# Microcontroller.net
KiCad netlist of a schematic drawn in Altium Designer
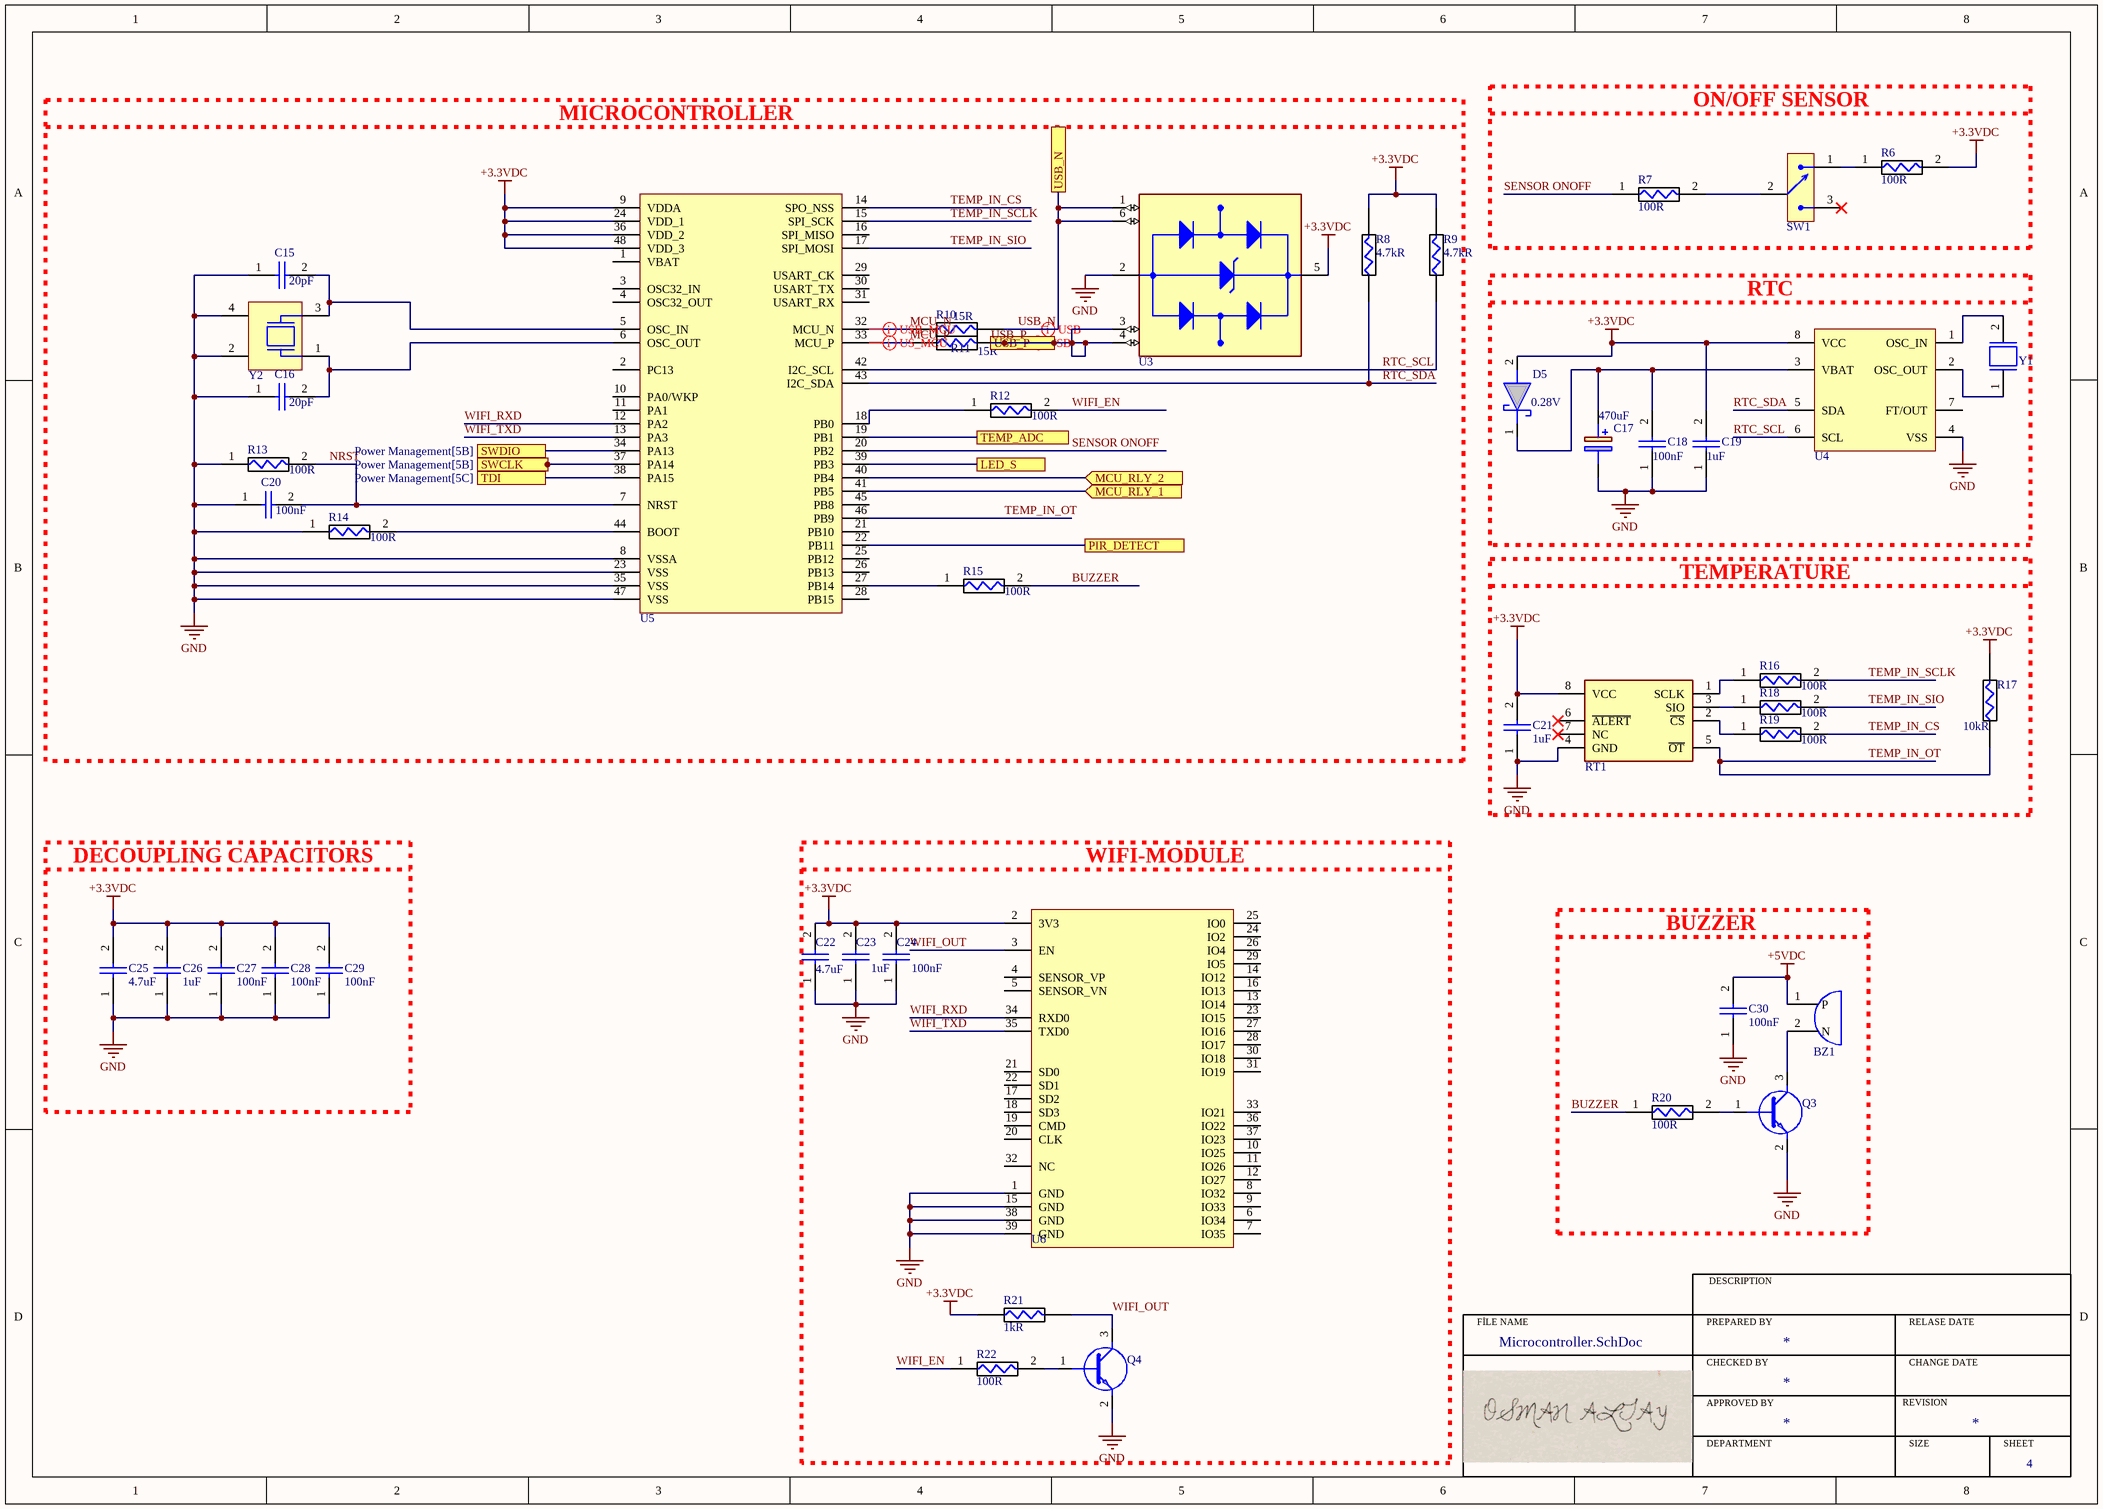
[diagram p0: Microcontroller.SchDoc]

(export (version "E")
  (design (tool "Eeschema 10.0.6"))
  (components
    (comp (ref "BZ1")
      (value "CMI-9605IC-0580T")
      (footprint "CMI-9605IC-0580T")
      (description "Audio Buzzer Magnetic 3VDC 7VDC 30mA 5VDC 85dB 2600Hz to 2800Hz Through Hole Pin Box")
      (fields (field (name "MANUFACTURER") "CUI Devices"))
      (libsource (lib "udemy_library") (part "CMI-9605IC-0580T"))
    )
    (comp (ref "C15")
      (value "20pF")
      (footprint "CAP_0603")
      (description "CAP CER 20pF %5 0603")
      (fields
        (field (name "MANUFACTURER") "Samsung")
        (field (name "MANUFACTURER PART NUMBER") "CL10C200JB8NNNC")
        (field (name "DESIGNED BY") "Osman")
      )
      (libsource (lib "udemy_library") (part "CAP CER 20pF 0603"))
    )
    (comp (ref "C16")
      (value "20pF")
      (footprint "CAP_0603")
      (description "CAP CER 20pF %5 0603")
      (fields
        (field (name "MANUFACTURER") "Samsung")
        (field (name "MANUFACTURER PART NUMBER") "CL10C200JB8NNNC")
        (field (name "DESIGNED BY") "Osman")
      )
      (libsource (lib "udemy_library") (part "CAP CER 20pF 0603"))
    )
    (comp (ref "C17")
      (value "470uF")
      (footprint "ESH477M050AH4AA")
      (description "Cap, 470UF, 50V, Alu Elec, Radial")
      (fields
        (field (name "MANUFACTURER") "KEMET")
        (field (name "MANUFACTURER PART NUMBER") "ESH477M050AH4AA")
        (field (name "DESIGNED BY") "Osman")
      )
      (libsource (lib "udemy_library") (part "CAP ALU 470uF"))
    )
    (comp (ref "C18")
      (value "100nF")
      (footprint "CAP_0805")
      (description "CL21B104KBCNNNC")
      (fields
        (field (name "MANUFACTURER") "Samsung")
        (field (name "TOLERANCE") "10%")
        (field (name "DESIGNED BY") "OSMAN")
      )
      (libsource (lib "udemy_library") (part "CAP CER 100nF 0805"))
    )
    (comp (ref "C19")
      (value "1uF")
      (footprint "CAP_0805")
      (description "CAP CER 1uF %10 0805")
      (fields
        (field (name "MANUFACTURER") "Samsung")
        (field (name "MANUFACTURER PART NUMBER") "CL21B105KBFNNNE")
        (field (name "DESIGNED BY") "Osman")
      )
      (libsource (lib "udemy_library") (part "CAP CER 1uF 0805"))
    )
    (comp (ref "C20")
      (value "100nF")
      (footprint "CAP_0603")
      (description "Capacitor, 0.1UF, 100V, MLCC, 0603;")
      (fields
        (field (name "MANUFACTURER") "KEMET")
        (field (name "MANUFACTURER PART NUMBER") "C0603C104K1RACTU")
        (field (name "DESIGNED BY") "Osman")
      )
      (libsource (lib "udemy_library") (part "CAP CER 100nf 0603"))
    )
    (comp (ref "C21")
      (value "1uF")
      (footprint "CAP_0805")
      (description "CAP CER 1uF %10 0805")
      (fields
        (field (name "MANUFACTURER") "Samsung")
        (field (name "MANUFACTURER PART NUMBER") "CL21B105KBFNNNE")
        (field (name "DESIGNED BY") "Osman")
      )
      (libsource (lib "udemy_library") (part "CAP CER 1uF 0805"))
    )
    (comp (ref "C22")
      (value "4.7uF")
      (footprint "CAP_0805")
      (description "CAP CER 4.7uF %10 0805")
      (fields
        (field (name "MANUFACTURER") "Samsung")
        (field (name "MANUFACTURER PART NUMBER") "CL21A475KAQNNNE")
      )
      (libsource (lib "udemy_library") (part "CAP CER 4.7uF 0805"))
    )
    (comp (ref "C23")
      (value "1uF")
      (footprint "CAP_0805")
      (description "CAP CER 1uF %10 0805")
      (fields
        (field (name "MANUFACTURER") "Samsung")
        (field (name "MANUFACTURER PART NUMBER") "CL21B105KBFNNNE")
        (field (name "DESIGNED BY") "Osman")
      )
      (libsource (lib "udemy_library") (part "CAP CER 1uF 0805"))
    )
    (comp (ref "C24")
      (value "100nF")
      (footprint "CAP_0603")
      (description "Capacitor, 0.1UF, 100V, MLCC, 0603;")
      (fields
        (field (name "MANUFACTURER") "KEMET")
        (field (name "MANUFACTURER PART NUMBER") "C0603C104K1RACTU")
        (field (name "DESIGNED BY") "Osman")
      )
      (libsource (lib "udemy_library") (part "CAP CER 100nf 0603"))
    )
    (comp (ref "C25")
      (value "4.7uF")
      (footprint "CAP_0805")
      (description "CAP CER 4.7uF %10 0805")
      (fields
        (field (name "MANUFACTURER") "Samsung")
        (field (name "MANUFACTURER PART NUMBER") "CL21A475KAQNNNE")
      )
      (libsource (lib "udemy_library") (part "CAP CER 4.7uF 0805"))
    )
    (comp (ref "C26")
      (value "1uF")
      (footprint "CAP_0805")
      (description "CAP CER 1uF %10 0805")
      (fields
        (field (name "MANUFACTURER") "Samsung")
        (field (name "MANUFACTURER PART NUMBER") "CL21B105KBFNNNE")
        (field (name "DESIGNED BY") "Osman")
      )
      (libsource (lib "udemy_library") (part "CAP CER 1uF 0805"))
    )
    (comp (ref "C27")
      (value "100nF")
      (footprint "CAP_0603")
      (description "Capacitor, 0.1UF, 100V, MLCC, 0603;")
      (fields
        (field (name "MANUFACTURER") "KEMET")
        (field (name "MANUFACTURER PART NUMBER") "C0603C104K1RACTU")
        (field (name "DESIGNED BY") "Osman")
      )
      (libsource (lib "udemy_library") (part "CAP CER 100nf 0603"))
    )
    (comp (ref "C28")
      (value "100nF")
      (footprint "CAP_0603")
      (description "Capacitor, 0.1UF, 100V, MLCC, 0603;")
      (fields
        (field (name "MANUFACTURER") "KEMET")
        (field (name "MANUFACTURER PART NUMBER") "C0603C104K1RACTU")
        (field (name "DESIGNED BY") "Osman")
      )
      (libsource (lib "udemy_library") (part "CAP CER 100nf 0603"))
    )
    (comp (ref "C29")
      (value "100nF")
      (footprint "CAP_0603")
      (description "Capacitor, 0.1UF, 100V, MLCC, 0603;")
      (fields
        (field (name "MANUFACTURER") "KEMET")
        (field (name "MANUFACTURER PART NUMBER") "C0603C104K1RACTU")
        (field (name "DESIGNED BY") "Osman")
      )
      (libsource (lib "udemy_library") (part "CAP CER 100nf 0603"))
    )
    (comp (ref "C30")
      (value "100nF")
      (footprint "CAP_0805")
      (description "CL21B104KBCNNNC")
      (fields
        (field (name "MANUFACTURER") "Samsung")
        (field (name "TOLERANCE") "10%")
        (field (name "DESIGNED BY") "OSMAN")
      )
      (libsource (lib "udemy_library") (part "CAP CER 100nF 0805"))
    )
    (comp (ref "D5")
      (value "RB521CS30L,315")
      (footprint "SOD882")
      (description "100MA Low Vf Mega Schottky Barri")
      (fields
        (field (name "MANUFACTURER") "Nexperia")
        (field (name "MANUFACTURER PART NUMBER") "RB521CS30L315")
        (field (name "FORWARD VOLTAGE") "0.28V")
      )
      (libsource (lib "udemy_library") (part "RB521CS30L,315"))
    )
    (comp (ref "Q3")
      (value "MMBT3904-7-F")
      (footprint "SOT23-3")
      (description "Transistor General Purpose BJT NPN 40 Volt 0.2A Automotive 3-Pin SOT-23")
      (fields (field (name "MANUFACTURER") "Diodes Zetex") (field (name "DESIGNED BY") "Osman"))
      (libsource (lib "udemy_library") (part "MMBT3904-7-F"))
    )
    (comp (ref "Q4")
      (value "MMBT3904-7-F")
      (footprint "SOT23-3")
      (description "Transistor General Purpose BJT NPN 40 Volt 0.2A Automotive 3-Pin SOT-23")
      (fields (field (name "MANUFACTURER") "Diodes Zetex") (field (name "DESIGNED BY") "Osman"))
      (libsource (lib "udemy_library") (part "MMBT3904-7-F"))
    )
    (comp (ref "R6")
      (value "100R")
      (footprint "RES_0603")
      (description "SMD Chip Resistor, 100 Ohm, ± 1%, 100 mW, 0603 [1608 Metric], Thick Film, General Purpose")
      (fields
        (field (name "MANUFACTURER") "Yageo")
        (field (name "MANUFACTURER PART NUMBER") "RC0603FR-07100RL")
      )
      (libsource (lib "udemy_library") (part "RES 100 OHM 0603"))
    )
    (comp (ref "R7")
      (value "100R")
      (footprint "RES_0603")
      (description "SMD Chip Resistor, 100 Ohm, ± 1%, 100 mW, 0603 [1608 Metric], Thick Film, General Purpose")
      (fields
        (field (name "MANUFACTURER") "Yageo")
        (field (name "MANUFACTURER PART NUMBER") "RC0603FR-07100RL")
      )
      (libsource (lib "udemy_library") (part "RES 100 OHM 0603"))
    )
    (comp (ref "R8")
      (value "4.7kR")
      (footprint "RES_0603")
      (description "SMD Chip Resistor, 4.7 kOhm, ± 5%, 100 mW, 0603 [1608 Metric], Thick Film, General Purpose")
      (fields
        (field (name "MANUFACTURER") "Yageo")
        (field (name "MANUFACTURER PART NUMBER") "RC0603JR-074K7L")
      )
      (libsource (lib "udemy_library") (part "RES 4K7 OHM 0603"))
    )
    (comp (ref "R9")
      (value "4.7kR")
      (footprint "RES_0603")
      (description "SMD Chip Resistor, 4.7 kOhm, ± 5%, 100 mW, 0603 [1608 Metric], Thick Film, General Purpose")
      (fields
        (field (name "MANUFACTURER") "Yageo")
        (field (name "MANUFACTURER PART NUMBER") "RC0603JR-074K7L")
      )
      (libsource (lib "udemy_library") (part "RES 4K7 OHM 0603"))
    )
    (comp (ref "R10")
      (value "15R")
      (footprint "RES_0603")
      (description "SMD Chip Resistor, 15 Ohm, ± 5%, 100 mW, 0603 [1608 Metric], Thick Film, General Purpose")
      (fields
        (field (name "MANUFACTURER") "Yageo")
        (field (name "MANUFACTURER PART NUMBER") "RC0603JR-0715RL")
      )
      (libsource (lib "udemy_library") (part "RES 15 OHM 0603"))
    )
    (comp (ref "R11")
      (value "15R")
      (footprint "RES_0603")
      (description "SMD Chip Resistor, 15 Ohm, ± 5%, 100 mW, 0603 [1608 Metric], Thick Film, General Purpose")
      (fields
        (field (name "MANUFACTURER") "Yageo")
        (field (name "MANUFACTURER PART NUMBER") "RC0603JR-0715RL")
      )
      (libsource (lib "udemy_library") (part "RES 15 OHM 0603"))
    )
    (comp (ref "R12")
      (value "100R")
      (footprint "RES_0603")
      (description "SMD Chip Resistor, 100 Ohm, ± 1%, 100 mW, 0603 [1608 Metric], Thick Film, General Purpose")
      (fields
        (field (name "MANUFACTURER") "Yageo")
        (field (name "MANUFACTURER PART NUMBER") "RC0603FR-07100RL")
      )
      (libsource (lib "udemy_library") (part "RES 100 OHM 0603"))
    )
    (comp (ref "R13")
      (value "100R")
      (footprint "RES_0603")
      (description "SMD Chip Resistor, 100 Ohm, ± 1%, 100 mW, 0603 [1608 Metric], Thick Film, General Purpose")
      (fields
        (field (name "MANUFACTURER") "Yageo")
        (field (name "MANUFACTURER PART NUMBER") "RC0603FR-07100RL")
      )
      (libsource (lib "udemy_library") (part "RES 100 OHM 0603"))
    )
    (comp (ref "R14")
      (value "100R")
      (footprint "RES_0603")
      (description "SMD Chip Resistor, 100 Ohm, ± 1%, 100 mW, 0603 [1608 Metric], Thick Film, General Purpose")
      (fields
        (field (name "MANUFACTURER") "Yageo")
        (field (name "MANUFACTURER PART NUMBER") "RC0603FR-07100RL")
      )
      (libsource (lib "udemy_library") (part "RES 100 OHM 0603"))
    )
    (comp (ref "R15")
      (value "100R")
      (footprint "RES_0603")
      (description "SMD Chip Resistor, 100 Ohm, ± 1%, 100 mW, 0603 [1608 Metric], Thick Film, General Purpose")
      (fields
        (field (name "MANUFACTURER") "Yageo")
        (field (name "MANUFACTURER PART NUMBER") "RC0603FR-07100RL")
      )
      (libsource (lib "udemy_library") (part "RES 100 OHM 0603"))
    )
    (comp (ref "R16")
      (value "100R")
      (footprint "RES_0603")
      (description "SMD Chip Resistor, 100 Ohm, ± 1%, 100 mW, 0603 [1608 Metric], Thick Film, General Purpose")
      (fields
        (field (name "MANUFACTURER") "Yageo")
        (field (name "MANUFACTURER PART NUMBER") "RC0603FR-07100RL")
      )
      (libsource (lib "udemy_library") (part "RES 100 OHM 0603"))
    )
    (comp (ref "R17")
      (value "10kR")
      (footprint "RES_0603")
      (description "RES 10K OHM %10 0603")
      (fields
        (field (name "MANUFACTURER") "Yageo")
        (field (name "MANUFACTURER PART NUMBER") "RC0603FR-0710KL")
        (field (name "DESIGNED NY") "Osman")
      )
      (libsource (lib "udemy_library") (part "RES 10K Ohm 0603"))
    )
    (comp (ref "R18")
      (value "100R")
      (footprint "RES_0603")
      (description "SMD Chip Resistor, 100 Ohm, ± 1%, 100 mW, 0603 [1608 Metric], Thick Film, General Purpose")
      (fields
        (field (name "MANUFACTURER") "Yageo")
        (field (name "MANUFACTURER PART NUMBER") "RC0603FR-07100RL")
      )
      (libsource (lib "udemy_library") (part "RES 100 OHM 0603"))
    )
    (comp (ref "R19")
      (value "100R")
      (footprint "RES_0603")
      (description "SMD Chip Resistor, 100 Ohm, ± 1%, 100 mW, 0603 [1608 Metric], Thick Film, General Purpose")
      (fields
        (field (name "MANUFACTURER") "Yageo")
        (field (name "MANUFACTURER PART NUMBER") "RC0603FR-07100RL")
      )
      (libsource (lib "udemy_library") (part "RES 100 OHM 0603"))
    )
    (comp (ref "R20")
      (value "100R")
      (footprint "RES_0603")
      (description "SMD Chip Resistor, 100 Ohm, ± 1%, 100 mW, 0603 [1608 Metric], Thick Film, General Purpose")
      (fields
        (field (name "MANUFACTURER") "Yageo")
        (field (name "MANUFACTURER PART NUMBER") "RC0603FR-07100RL")
      )
      (libsource (lib "udemy_library") (part "RES 100 OHM 0603"))
    )
    (comp (ref "R21")
      (value "1kR")
      (footprint "RES_0603")
      (description "Res Thick Film 0201 1K Ohm 5% 0.05W(1/20W) ±200ppm/C Pad SMD T/R")
      (fields
        (field (name "MANUFACTURER") "Yageo")
        (field (name "MANUFACTURER PART NUMBER") "RC0201JR-071KL")
      )
      (libsource (lib "udemy_library") (part "RES 1K OHM 0603"))
    )
    (comp (ref "R22")
      (value "100R")
      (footprint "RES_0603")
      (description "SMD Chip Resistor, 100 Ohm, ± 1%, 100 mW, 0603 [1608 Metric], Thick Film, General Purpose")
      (fields
        (field (name "MANUFACTURER") "Yageo")
        (field (name "MANUFACTURER PART NUMBER") "RC0603FR-07100RL")
      )
      (libsource (lib "udemy_library") (part "RES 100 OHM 0603"))
    )
    (comp (ref "RT1")
      (value "MAX6662MSA+")
      (footprint "MAX6662MSA+")
      (description "Temp Sensor Digital Serial (3-Wire, SPI) 8-Pin SOIC N Tube")
      (fields (field (name "MANUFACTURER") "Maxim") (field (name "DESIGNED BY") "Osman"))
      (libsource (lib "udemy_library") (part "MAX6662MSA+"))
    )
    (comp (ref "SW1")
      (value "EG1215AA")
      (footprint "SW_EG1215AA")
      (description "Slide Switch, SPDT, 0.025A, 24V, SMD")
      (fields (field (name "MANUFACTURER") "E-Switch"))
      (libsource (lib "udemy_library") (part "EG1215AA"))
    )
    (comp (ref "U3")
      (value "USBLC6-2SC6")
      (footprint "SOT23-6")
      (description "USBLC6 Series 2 Line 6 V Uni / Bi-Directional ESD Protection - SOT-23-6")
      (fields (field (name "MANUFACTURER") "STMicroelectronics"))
      (libsource (lib "udemy_library") (part "USBLC6-2SC6"))
    )
    (comp (ref "U4")
      (value "M41T00M6F")
      (footprint "M41T00")
      (description "Real-time Clocks Clock/Calendar I2C, 2-Wire Serial 70uA @ 2V ~ 5.5V SOIC-8_150mil RoHS")
      (fields (field (name "MANUFACTURER") "STMicroelectronics"))
      (libsource (lib "udemy_library") (part "M41T00"))
    )
    (comp (ref "U5")
      (value "STM32F103C6T6A")
      (footprint "LQFP-48")
      (description "MCU 32-bit STM32F ARM Cortex M3 RISC 32KB Flash 2.5V/3.3V 48-Pin LQFP Tray")
      (fields (field (name "MANUFACTURER") "STMicroelectronics"))
      (libsource (lib "udemy_library") (part "STM32F103C6T6A"))
    )
    (comp (ref "U6")
      (value "ESP32-WROOM-32")
      (footprint "ESP32")
      (description "SMD module, ESP32-D0WD-V3, ESP32 ECO V3, 4 MB SPI flash, PCB antenna")
      (fields
        (field (name "MANUFACTURER") "Espressif Systems")
        (field (name "MANUFACTURER PART NUMBER") "ESP32-WROOM-32E(M113EH3200PH3Q0)")
        (field (name "DESIGNED NY") "Osman")
      )
      (libsource (lib "udemy_library") (part "ESP32-WROOM-32"))
    )
    (comp (ref "Y1")
      (value "ABS05-32.768KHZ-T")
      (footprint "ABS05")
      (description "CRYSTAL 32.768kHz ±20ppm Crystal 12.5pF 90 kOhm -40°C ^ 85°C Surface Mount 2-SMD")
      (fields (field (name "MANUFACTURER") "Abracon") (field (name "TOLERANCE") "20ppm"))
      (libsource (lib "udemy_library") (part "Crystal 32768KHz"))
    )
    (comp (ref "Y2")
      (value "ECS-160-20-30B-TR")
      (footprint "ECS")
      (description "Crystal 16MHz ±30ppm (Tol) ±50ppm (Stability) 20pF FUND 50Ohm 4-Pin Mini-SMD T/R")
      (fields (field (name "MANUFACTURER") "ECS International"))
      (libsource (lib "udemy_library") (part "Crystal 16MHz"))
    )
  )
  (nets
    (net (code "1") (name "+3.3VDC") (class "Default")
      (node (ref "C19") (pin "2") (pinfunction "2_2") (pintype "passive"))
      (node (ref "C21") (pin "2") (pinfunction "2_2") (pintype "passive"))
      (node (ref "C22") (pin "2") (pinfunction "2_2") (pintype "passive"))
      (node (ref "C23") (pin "2") (pinfunction "2_2") (pintype "passive"))
      (node (ref "C24") (pin "2") (pinfunction "2_2") (pintype "passive"))
      (node (ref "C25") (pin "2") (pinfunction "2_2") (pintype "passive"))
      (node (ref "C26") (pin "2") (pinfunction "2_2") (pintype "passive"))
      (node (ref "C27") (pin "2") (pinfunction "2_2") (pintype "passive"))
      (node (ref "C28") (pin "2") (pinfunction "2_2") (pintype "passive"))
      (node (ref "C29") (pin "2") (pinfunction "2_2") (pintype "passive"))
      (node (ref "D5") (pin "2") (pinfunction "A_2") (pintype "passive"))
      (node (ref "R17") (pin "2") (pinfunction "2_2") (pintype "passive"))
      (node (ref "R21") (pin "1") (pinfunction "1_1") (pintype "passive"))
      (node (ref "R6") (pin "2") (pinfunction "2_2") (pintype "passive"))
      (node (ref "R8") (pin "2") (pinfunction "2_2") (pintype "passive"))
      (node (ref "R9") (pin "2") (pinfunction "2_2") (pintype "passive"))
      (node (ref "RT1") (pin "8") (pinfunction "VCC_8") (pintype "passive"))
      (node (ref "U3") (pin "5") (pinfunction "VBUS_5") (pintype "power_in"))
      (node (ref "U4") (pin "8") (pinfunction "VCC_8") (pintype "passive"))
      (node (ref "U5") (pin "24") (pinfunction "VDD_1_24") (pintype "passive"))
      (node (ref "U5") (pin "36") (pinfunction "VDD_2_36") (pintype "passive"))
      (node (ref "U5") (pin "48") (pinfunction "VDD_3_48") (pintype "passive"))
      (node (ref "U5") (pin "9") (pinfunction "VDDA_9") (pintype "passive"))
      (node (ref "U6") (pin "2") (pinfunction "3V3_2") (pintype "passive"))
    )
    (net (code "2") (name "+5VDC") (class "Default")
      (node (ref "BZ1") (pin "1") (pinfunction "P_1") (pintype "passive"))
      (node (ref "C30") (pin "2") (pinfunction "2_2") (pintype "passive"))
    )
    (net (code "3") (name "/BUZZER") (class "Default")
      (node (ref "R15") (pin "2") (pinfunction "2_2") (pintype "passive"))
      (node (ref "R20") (pin "1") (pinfunction "1_1") (pintype "passive"))
    )
    (net (code "4") (name "/LED_S") (class "Default")
      (node (ref "U5") (pin "39") (pinfunction "PB3_39") (pintype "passive"))
    )
    (net (code "5") (name "/MCU_N") (class "Default")
      (node (ref "R10") (pin "1") (pinfunction "1_1") (pintype "passive"))
      (node (ref "U5") (pin "32") (pinfunction "MCU_N_32") (pintype "passive"))
    )
    (net (code "6") (name "/MCU_P") (class "Default")
      (node (ref "R11") (pin "1") (pinfunction "1_1") (pintype "passive"))
      (node (ref "U5") (pin "33") (pinfunction "MCU_P_33") (pintype "passive"))
    )
    (net (code "7") (name "/MCU_RLY_1") (class "Default")
      (node (ref "U5") (pin "41") (pinfunction "PB5_41") (pintype "passive"))
    )
    (net (code "8") (name "/MCU_RLY_2") (class "Default")
      (node (ref "U5") (pin "40") (pinfunction "PB4_40") (pintype "passive"))
    )
    (net (code "9") (name "/NRST") (class "Default")
      (node (ref "C20") (pin "2") (pinfunction "2_2") (pintype "passive"))
      (node (ref "R13") (pin "2") (pinfunction "2_2") (pintype "passive"))
      (node (ref "U5") (pin "7") (pinfunction "NRST_7") (pintype "passive"))
    )
    (net (code "10") (name "/PIR_DETECT") (class "Default")
      (node (ref "U5") (pin "22") (pinfunction "PB11_22") (pintype "passive"))
    )
    (net (code "11") (name "/RTC_SCL") (class "Default")
      (node (ref "R9") (pin "1") (pinfunction "1_1") (pintype "passive"))
      (node (ref "U4") (pin "6") (pinfunction "SCL_6") (pintype "passive"))
      (node (ref "U5") (pin "42") (pinfunction "I2C_SCL_42") (pintype "passive"))
    )
    (net (code "12") (name "/RTC_SDA") (class "Default")
      (node (ref "R8") (pin "1") (pinfunction "1_1") (pintype "passive"))
      (node (ref "U4") (pin "5") (pinfunction "SDA_5") (pintype "passive"))
      (node (ref "U5") (pin "43") (pinfunction "I2C_SDA_43") (pintype "passive"))
    )
    (net (code "13") (name "/SENSOR ONOFF") (class "Default")
      (node (ref "R7") (pin "1") (pinfunction "1_1") (pintype "passive"))
      (node (ref "U5") (pin "20") (pinfunction "PB2_20") (pintype "passive"))
    )
    (net (code "14") (name "/SWCLK") (class "Default")
      (node (ref "U5") (pin "37") (pinfunction "PA14_37") (pintype "passive"))
    )
    (net (code "15") (name "/SWDIO") (class "Default")
      (node (ref "U5") (pin "34") (pinfunction "PA13_34") (pintype "passive"))
    )
    (net (code "16") (name "/TDI") (class "Default")
      (node (ref "U5") (pin "38") (pinfunction "PA15_38") (pintype "passive"))
    )
    (net (code "17") (name "/TEMP_ADC") (class "Default")
      (node (ref "U5") (pin "19") (pinfunction "PB1_19") (pintype "passive"))
    )
    (net (code "18") (name "/TEMP_IN_CS") (class "Default")
      (node (ref "R19") (pin "2") (pinfunction "2_2") (pintype "passive"))
      (node (ref "U5") (pin "14") (pinfunction "SPO_NSS_14") (pintype "passive"))
    )
    (net (code "19") (name "/TEMP_IN_OT") (class "Default")
      (node (ref "R17") (pin "1") (pinfunction "1_1") (pintype "passive"))
      (node (ref "RT1") (pin "5") (pinfunction "~{OT}_5") (pintype "passive"))
      (node (ref "U5") (pin "46") (pinfunction "PB9_46") (pintype "passive"))
    )
    (net (code "20") (name "/TEMP_IN_SCLK") (class "Default")
      (node (ref "R16") (pin "2") (pinfunction "2_2") (pintype "passive"))
      (node (ref "U5") (pin "15") (pinfunction "SPI_SCK_15") (pintype "passive"))
    )
    (net (code "21") (name "/TEMP_IN_SIO") (class "Default")
      (node (ref "R18") (pin "2") (pinfunction "2_2") (pintype "passive"))
      (node (ref "U5") (pin "17") (pinfunction "SPI_MOSI_17") (pintype "passive"))
    )
    (net (code "22") (name "/USB_N") (class "Default")
      (node (ref "R10") (pin "2") (pinfunction "2_2") (pintype "passive"))
      (node (ref "U3") (pin "1") (pinfunction "I/O1_IN_1") (pintype "bidirectional"))
      (node (ref "U3") (pin "6") (pinfunction "I/O1_OUT_6") (pintype "bidirectional"))
    )
    (net (code "23") (name "/USB_P") (class "Default")
      (node (ref "R11") (pin "2") (pinfunction "2_2") (pintype "passive"))
      (node (ref "U3") (pin "3") (pinfunction "I/O2_IN_3") (pintype "bidirectional"))
      (node (ref "U3") (pin "4") (pinfunction "I/O2_OUT_4") (pintype "bidirectional"))
    )
    (net (code "24") (name "/WIFI_EN") (class "Default")
      (node (ref "R12") (pin "2") (pinfunction "2_2") (pintype "passive"))
      (node (ref "R22") (pin "1") (pinfunction "1_1") (pintype "passive"))
    )
    (net (code "25") (name "/WIFI_OUT") (class "Default")
      (node (ref "Q4") (pin "3") (pinfunction "C_3") (pintype "passive"))
      (node (ref "R21") (pin "2") (pinfunction "2_2") (pintype "passive"))
      (node (ref "U6") (pin "3") (pinfunction "EN_3") (pintype "passive"))
    )
    (net (code "26") (name "/WIFI_RXD") (class "Default")
      (node (ref "U5") (pin "12") (pinfunction "PA2_12") (pintype "passive"))
      (node (ref "U6") (pin "34") (pinfunction "RXD0_34") (pintype "passive"))
    )
    (net (code "27") (name "/WIFI_TXD") (class "Default")
      (node (ref "U5") (pin "13") (pinfunction "PA3_13") (pintype "passive"))
      (node (ref "U6") (pin "35") (pinfunction "TXD0_35") (pintype "passive"))
    )
    (net (code "28") (name "GND") (class "Default")
      (node (ref "C15") (pin "1") (pinfunction "1_1") (pintype "passive"))
      (node (ref "C16") (pin "1") (pinfunction "1_1") (pintype "passive"))
      (node (ref "C17") (pin "2") (pinfunction "-_2") (pintype "passive"))
      (node (ref "C18") (pin "1") (pinfunction "1_1") (pintype "passive"))
      (node (ref "C19") (pin "1") (pinfunction "1_1") (pintype "passive"))
      (node (ref "C20") (pin "1") (pinfunction "1_1") (pintype "passive"))
      (node (ref "C21") (pin "1") (pinfunction "1_1") (pintype "passive"))
      (node (ref "C22") (pin "1") (pinfunction "1_1") (pintype "passive"))
      (node (ref "C23") (pin "1") (pinfunction "1_1") (pintype "passive"))
      (node (ref "C24") (pin "1") (pinfunction "1_1") (pintype "passive"))
      (node (ref "C25") (pin "1") (pinfunction "1_1") (pintype "passive"))
      (node (ref "C26") (pin "1") (pinfunction "1_1") (pintype "passive"))
      (node (ref "C27") (pin "1") (pinfunction "1_1") (pintype "passive"))
      (node (ref "C28") (pin "1") (pinfunction "1_1") (pintype "passive"))
      (node (ref "C29") (pin "1") (pinfunction "1_1") (pintype "passive"))
      (node (ref "C30") (pin "1") (pinfunction "1_1") (pintype "passive"))
      (node (ref "Q3") (pin "2") (pinfunction "E_2") (pintype "passive"))
      (node (ref "Q4") (pin "2") (pinfunction "E_2") (pintype "passive"))
      (node (ref "R13") (pin "1") (pinfunction "1_1") (pintype "passive"))
      (node (ref "R14") (pin "1") (pinfunction "1_1") (pintype "passive"))
      (node (ref "RT1") (pin "4") (pinfunction "GND_4") (pintype "passive"))
      (node (ref "U3") (pin "2") (pinfunction "GND_2") (pintype "power_in"))
      (node (ref "U4") (pin "4") (pinfunction "VSS_4") (pintype "passive"))
      (node (ref "U5") (pin "23") (pinfunction "VSS_23") (pintype "passive"))
      (node (ref "U5") (pin "35") (pinfunction "VSS_35") (pintype "passive"))
      (node (ref "U5") (pin "47") (pinfunction "VSS_47") (pintype "passive"))
      (node (ref "U5") (pin "8") (pinfunction "VSSA_8") (pintype "passive"))
      (node (ref "U6") (pin "1") (pinfunction "GND_1") (pintype "passive"))
      (node (ref "U6") (pin "15") (pinfunction "GND_15") (pintype "passive"))
      (node (ref "U6") (pin "38") (pinfunction "GND_38") (pintype "passive"))
      (node (ref "U6") (pin "39") (pinfunction "GND_39") (pintype "passive"))
      (node (ref "Y2") (pin "2") (pinfunction "GND_2") (pintype "passive"))
      (node (ref "Y2") (pin "4") (pinfunction "GND_4") (pintype "passive"))
    )
    (net (code "29") (name "Net-(BZ1-N)") (class "Default")
      (node (ref "BZ1") (pin "2") (pinfunction "N_2") (pintype "passive"))
      (node (ref "Q3") (pin "3") (pinfunction "C_3") (pintype "passive"))
    )
    (net (code "30") (name "Net-(C17-+)") (class "Default")
      (node (ref "C17") (pin "1") (pinfunction "+_1") (pintype "passive"))
      (node (ref "C18") (pin "2") (pinfunction "2_2") (pintype "passive"))
      (node (ref "D5") (pin "1") (pinfunction "K_1") (pintype "passive"))
      (node (ref "U4") (pin "3") (pinfunction "VBAT_3") (pintype "passive"))
    )
    (net (code "31") (name "Net-(Q3-B)") (class "Default")
      (node (ref "Q3") (pin "1") (pinfunction "B_1") (pintype "passive"))
      (node (ref "R20") (pin "2") (pinfunction "2_2") (pintype "passive"))
    )
    (net (code "32") (name "Net-(Q4-B)") (class "Default")
      (node (ref "Q4") (pin "1") (pinfunction "B_1") (pintype "passive"))
      (node (ref "R22") (pin "2") (pinfunction "2_2") (pintype "passive"))
    )
    (net (code "33") (name "Net-(R6-Pad1)") (class "Default")
      (node (ref "R6") (pin "1") (pinfunction "1_1") (pintype "passive"))
      (node (ref "SW1") (pin "1") (pinfunction "1_1") (pintype "passive"))
    )
    (net (code "34") (name "Net-(R7-Pad2)") (class "Default")
      (node (ref "R7") (pin "2") (pinfunction "2_2") (pintype "passive"))
      (node (ref "SW1") (pin "2") (pinfunction "2_2") (pintype "passive"))
    )
    (net (code "35") (name "Net-(RT1-SCLK)") (class "Default")
      (node (ref "R16") (pin "1") (pinfunction "1_1") (pintype "passive"))
      (node (ref "RT1") (pin "1") (pinfunction "SCLK_1") (pintype "passive"))
    )
    (net (code "36") (name "Net-(RT1-SIO)") (class "Default")
      (node (ref "R18") (pin "1") (pinfunction "1_1") (pintype "passive"))
      (node (ref "RT1") (pin "3") (pinfunction "SIO_3") (pintype "passive"))
    )
    (net (code "37") (name "Net-(RT1-~{CS})") (class "Default")
      (node (ref "R19") (pin "1") (pinfunction "1_1") (pintype "passive"))
      (node (ref "RT1") (pin "2") (pinfunction "~{CS}_2") (pintype "passive"))
    )
    (net (code "38") (name "Net-(U4-OSC_IN)") (class "Default")
      (node (ref "U4") (pin "1") (pinfunction "OSC_IN_1") (pintype "passive"))
      (node (ref "Y1") (pin "2") (pinfunction "2_2") (pintype "passive"))
    )
    (net (code "39") (name "Net-(U4-OSC_OUT)") (class "Default")
      (node (ref "U4") (pin "2") (pinfunction "OSC_OUT_2") (pintype "passive"))
      (node (ref "Y1") (pin "1") (pinfunction "1_1") (pintype "passive"))
    )
    (net (code "40") (name "Net-(U5-BOOT)") (class "Default")
      (node (ref "R14") (pin "2") (pinfunction "2_2") (pintype "passive"))
      (node (ref "U5") (pin "44") (pinfunction "BOOT_44") (pintype "passive"))
    )
    (net (code "41") (name "Net-(U5-OSC_IN)") (class "Default")
      (node (ref "C15") (pin "2") (pinfunction "2_2") (pintype "passive"))
      (node (ref "U5") (pin "5") (pinfunction "OSC_IN_5") (pintype "passive"))
      (node (ref "Y2") (pin "3") (pinfunction "OUT/IN_3") (pintype "passive"))
    )
    (net (code "42") (name "Net-(U5-OSC_OUT)") (class "Default")
      (node (ref "C16") (pin "2") (pinfunction "2_2") (pintype "passive"))
      (node (ref "U5") (pin "6") (pinfunction "OSC_OUT_6") (pintype "passive"))
      (node (ref "Y2") (pin "1") (pinfunction "IN/OUT_1") (pintype "passive"))
    )
    (net (code "43") (name "Net-(U5-PB0)") (class "Default")
      (node (ref "R12") (pin "1") (pinfunction "1_1") (pintype "passive"))
      (node (ref "U5") (pin "18") (pinfunction "PB0_18") (pintype "passive"))
    )
    (net (code "44") (name "Net-(U5-PB14)") (class "Default")
      (node (ref "R15") (pin "1") (pinfunction "1_1") (pintype "passive"))
      (node (ref "U5") (pin "27") (pinfunction "PB14_27") (pintype "passive"))
    )
    (net (code "45") (name "unconnected-(RT1-NC-Pad7)") (class "Default")
      (node (ref "RT1") (pin "7") (pinfunction "NC_7") (pintype "passive+no_connect"))
    )
    (net (code "46") (name "unconnected-(RT1-~{ALERT}-Pad6)") (class "Default")
      (node (ref "RT1") (pin "6") (pinfunction "~{ALERT}_6") (pintype "passive+no_connect"))
    )
    (net (code "47") (name "unconnected-(SW1-Pad3)") (class "Default")
      (node (ref "SW1") (pin "3") (pinfunction "3_3") (pintype "passive+no_connect"))
    )
    (net (code "48") (name "unconnected-(U4-FT{slash}OUT-Pad7)") (class "Default")
      (node (ref "U4") (pin "7") (pinfunction "FT/OUT_7") (pintype "passive"))
    )
    (net (code "49") (name "unconnected-(U5-OSC32_IN-Pad3)") (class "Default")
      (node (ref "U5") (pin "3") (pinfunction "OSC32_IN_3") (pintype "passive"))
    )
    (net (code "50") (name "unconnected-(U5-OSC32_OUT-Pad4)") (class "Default")
      (node (ref "U5") (pin "4") (pinfunction "OSC32_OUT_4") (pintype "passive"))
    )
    (net (code "51") (name "unconnected-(U5-PA0{slash}WKP-Pad10)") (class "Default")
      (node (ref "U5") (pin "10") (pinfunction "PA0/WKP_10") (pintype "passive"))
    )
    (net (code "52") (name "unconnected-(U5-PA1-Pad11)") (class "Default")
      (node (ref "U5") (pin "11") (pinfunction "PA1_11") (pintype "passive"))
    )
    (net (code "53") (name "unconnected-(U5-PB8-Pad45)") (class "Default")
      (node (ref "U5") (pin "45") (pinfunction "PB8_45") (pintype "passive"))
    )
    (net (code "54") (name "unconnected-(U5-PB10-Pad21)") (class "Default")
      (node (ref "U5") (pin "21") (pinfunction "PB10_21") (pintype "passive"))
    )
    (net (code "55") (name "unconnected-(U5-PB12-Pad25)") (class "Default")
      (node (ref "U5") (pin "25") (pinfunction "PB12_25") (pintype "passive"))
    )
    (net (code "56") (name "unconnected-(U5-PB13-Pad26)") (class "Default")
      (node (ref "U5") (pin "26") (pinfunction "PB13_26") (pintype "passive"))
    )
    (net (code "57") (name "unconnected-(U5-PB15-Pad28)") (class "Default")
      (node (ref "U5") (pin "28") (pinfunction "PB15_28") (pintype "passive"))
    )
    (net (code "58") (name "unconnected-(U5-PC13-Pad2)") (class "Default")
      (node (ref "U5") (pin "2") (pinfunction "PC13_2") (pintype "passive"))
    )
    (net (code "59") (name "unconnected-(U5-SPI_MISO-Pad16)") (class "Default")
      (node (ref "U5") (pin "16") (pinfunction "SPI_MISO_16") (pintype "passive"))
    )
    (net (code "60") (name "unconnected-(U5-USART_CK-Pad29)") (class "Default")
      (node (ref "U5") (pin "29") (pinfunction "USART_CK_29") (pintype "passive"))
    )
    (net (code "61") (name "unconnected-(U5-USART_RX-Pad31)") (class "Default")
      (node (ref "U5") (pin "31") (pinfunction "USART_RX_31") (pintype "passive"))
    )
    (net (code "62") (name "unconnected-(U5-USART_TX-Pad30)") (class "Default")
      (node (ref "U5") (pin "30") (pinfunction "USART_TX_30") (pintype "passive"))
    )
    (net (code "63") (name "unconnected-(U5-VBAT-Pad1)") (class "Default")
      (node (ref "U5") (pin "1") (pinfunction "VBAT_1") (pintype "passive"))
    )
    (net (code "64") (name "unconnected-(U6-CLK-Pad20)") (class "Default")
      (node (ref "U6") (pin "20") (pinfunction "CLK_20") (pintype "passive"))
    )
    (net (code "65") (name "unconnected-(U6-CMD-Pad19)") (class "Default")
      (node (ref "U6") (pin "19") (pinfunction "CMD_19") (pintype "passive"))
    )
    (net (code "66") (name "unconnected-(U6-IO0-Pad25)") (class "Default")
      (node (ref "U6") (pin "25") (pinfunction "IO0_25") (pintype "passive"))
    )
    (net (code "67") (name "unconnected-(U6-IO2-Pad24)") (class "Default")
      (node (ref "U6") (pin "24") (pinfunction "IO2_24") (pintype "passive"))
    )
    (net (code "68") (name "unconnected-(U6-IO4-Pad26)") (class "Default")
      (node (ref "U6") (pin "26") (pinfunction "IO4_26") (pintype "passive"))
    )
    (net (code "69") (name "unconnected-(U6-IO5-Pad29)") (class "Default")
      (node (ref "U6") (pin "29") (pinfunction "IO5_29") (pintype "passive"))
    )
    (net (code "70") (name "unconnected-(U6-IO12-Pad14)") (class "Default")
      (node (ref "U6") (pin "14") (pinfunction "IO12_14") (pintype "passive"))
    )
    (net (code "71") (name "unconnected-(U6-IO13-Pad16)") (class "Default")
      (node (ref "U6") (pin "16") (pinfunction "IO13_16") (pintype "passive"))
    )
    (net (code "72") (name "unconnected-(U6-IO14-Pad13)") (class "Default")
      (node (ref "U6") (pin "13") (pinfunction "IO14_13") (pintype "passive"))
    )
    (net (code "73") (name "unconnected-(U6-IO15-Pad23)") (class "Default")
      (node (ref "U6") (pin "23") (pinfunction "IO15_23") (pintype "passive"))
    )
    (net (code "74") (name "unconnected-(U6-IO16-Pad27)") (class "Default")
      (node (ref "U6") (pin "27") (pinfunction "IO16_27") (pintype "passive"))
    )
    (net (code "75") (name "unconnected-(U6-IO17-Pad28)") (class "Default")
      (node (ref "U6") (pin "28") (pinfunction "IO17_28") (pintype "passive"))
    )
    (net (code "76") (name "unconnected-(U6-IO18-Pad30)") (class "Default")
      (node (ref "U6") (pin "30") (pinfunction "IO18_30") (pintype "passive"))
    )
    (net (code "77") (name "unconnected-(U6-IO19-Pad31)") (class "Default")
      (node (ref "U6") (pin "31") (pinfunction "IO19_31") (pintype "passive"))
    )
    (net (code "78") (name "unconnected-(U6-IO21-Pad33)") (class "Default")
      (node (ref "U6") (pin "33") (pinfunction "IO21_33") (pintype "passive"))
    )
    (net (code "79") (name "unconnected-(U6-IO22-Pad36)") (class "Default")
      (node (ref "U6") (pin "36") (pinfunction "IO22_36") (pintype "passive"))
    )
    (net (code "80") (name "unconnected-(U6-IO23-Pad37)") (class "Default")
      (node (ref "U6") (pin "37") (pinfunction "IO23_37") (pintype "passive"))
    )
    (net (code "81") (name "unconnected-(U6-IO25-Pad10)") (class "Default")
      (node (ref "U6") (pin "10") (pinfunction "IO25_10") (pintype "passive"))
    )
    (net (code "82") (name "unconnected-(U6-IO26-Pad11)") (class "Default")
      (node (ref "U6") (pin "11") (pinfunction "IO26_11") (pintype "passive"))
    )
    (net (code "83") (name "unconnected-(U6-IO27-Pad12)") (class "Default")
      (node (ref "U6") (pin "12") (pinfunction "IO27_12") (pintype "passive"))
    )
    (net (code "84") (name "unconnected-(U6-IO32-Pad8)") (class "Default")
      (node (ref "U6") (pin "8") (pinfunction "IO32_8") (pintype "passive"))
    )
    (net (code "85") (name "unconnected-(U6-IO33-Pad9)") (class "Default")
      (node (ref "U6") (pin "9") (pinfunction "IO33_9") (pintype "passive"))
    )
    (net (code "86") (name "unconnected-(U6-IO34-Pad6)") (class "Default")
      (node (ref "U6") (pin "6") (pinfunction "IO34_6") (pintype "passive"))
    )
    (net (code "87") (name "unconnected-(U6-IO35-Pad7)") (class "Default")
      (node (ref "U6") (pin "7") (pinfunction "IO35_7") (pintype "passive"))
    )
    (net (code "88") (name "unconnected-(U6-NC-Pad32)") (class "Default")
      (node (ref "U6") (pin "32") (pinfunction "NC_32") (pintype "passive"))
    )
    (net (code "89") (name "unconnected-(U6-SD0-Pad21)") (class "Default")
      (node (ref "U6") (pin "21") (pinfunction "SD0_21") (pintype "passive"))
    )
    (net (code "90") (name "unconnected-(U6-SD1-Pad22)") (class "Default")
      (node (ref "U6") (pin "22") (pinfunction "SD1_22") (pintype "passive"))
    )
    (net (code "91") (name "unconnected-(U6-SD2-Pad17)") (class "Default")
      (node (ref "U6") (pin "17") (pinfunction "SD2_17") (pintype "passive"))
    )
    (net (code "92") (name "unconnected-(U6-SD3-Pad18)") (class "Default")
      (node (ref "U6") (pin "18") (pinfunction "SD3_18") (pintype "passive"))
    )
    (net (code "93") (name "unconnected-(U6-SENSOR_VN-Pad5)") (class "Default")
      (node (ref "U6") (pin "5") (pinfunction "SENSOR_VN_5") (pintype "passive"))
    )
    (net (code "94") (name "unconnected-(U6-SENSOR_VP-Pad4)") (class "Default")
      (node (ref "U6") (pin "4") (pinfunction "SENSOR_VP_4") (pintype "passive"))
    )
  )
)
